# hm2_redraw.net
KiCad netlist of a schematic drawn in EAGLE
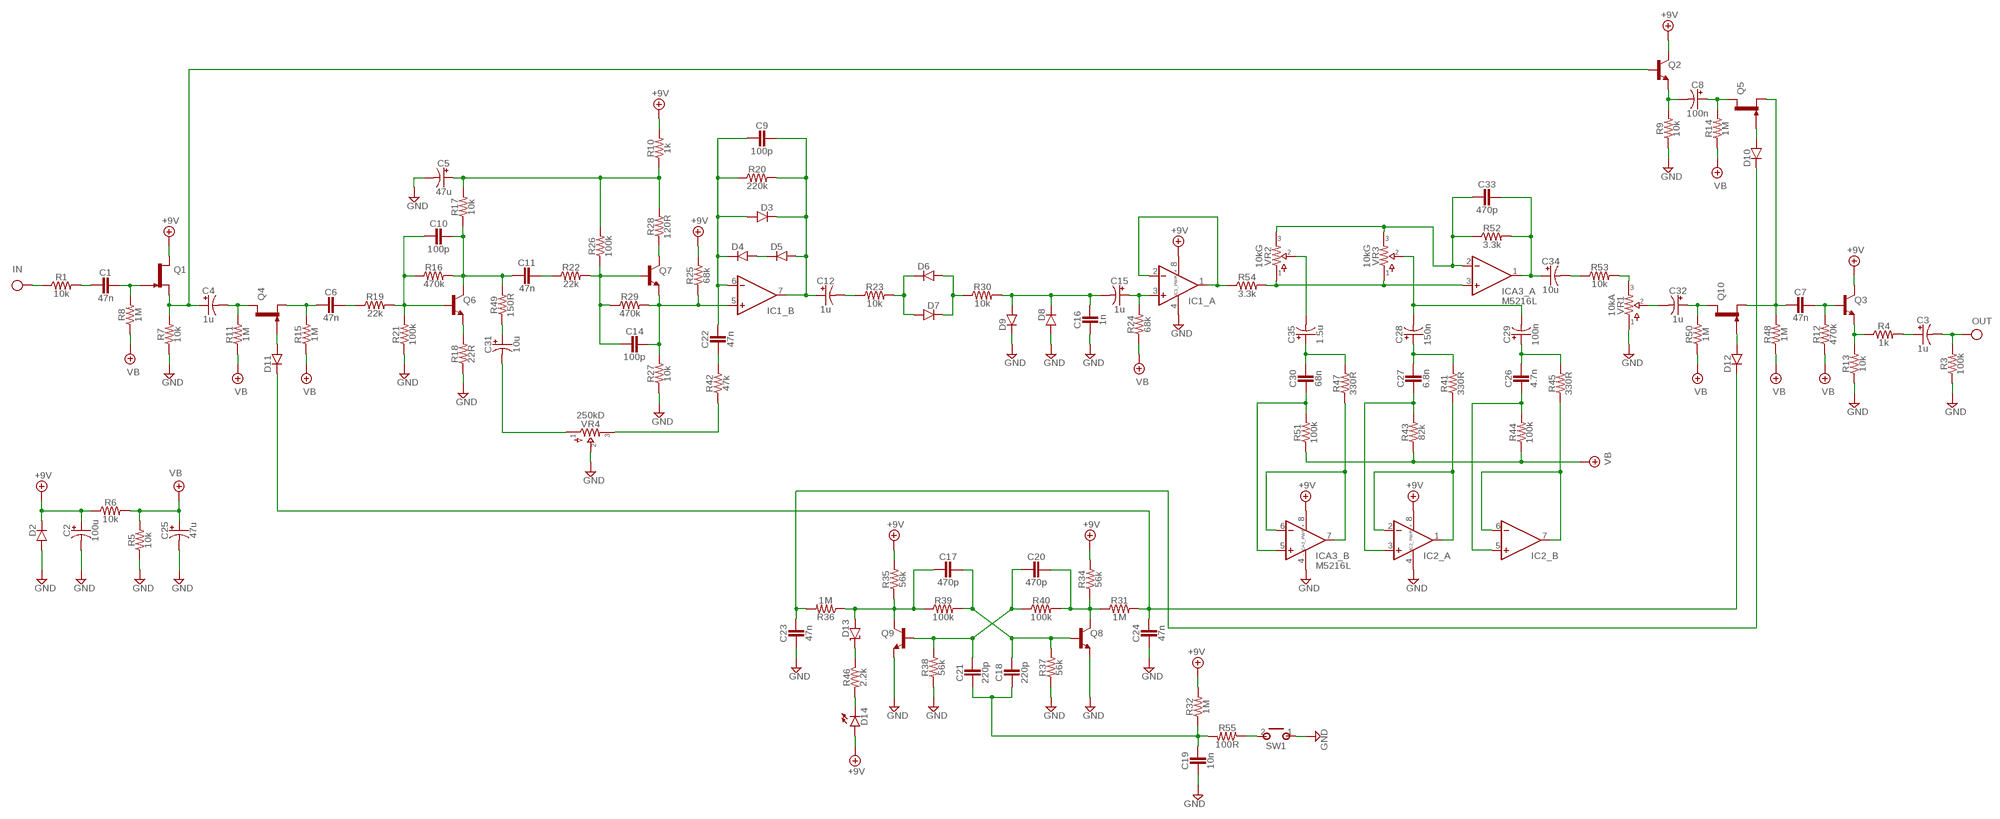
[diagram p0: schematic, sheet 1]

(export (version "E")
  (design (tool "Eeschema 10.0.6"))
  (components
    (comp (ref "C1")
      (value "47n")
      (footprint "eagle-import:BOX_SMALL")
      (libsource (lib "eagle-import") (part "CER/FILMBOX.1"))
    )
    (comp (ref "C2")
      (value "100u")
      (footprint "eagle-import:040_020")
      (libsource (lib "eagle-import") (part "0400"))
    )
    (comp (ref "C3")
      (value "1u")
      (footprint "eagle-import:040_020")
      (libsource (lib "eagle-import") (part "0400"))
    )
    (comp (ref "C4")
      (value "1u")
      (footprint "eagle-import:040_020")
      (libsource (lib "eagle-import") (part "0400"))
    )
    (comp (ref "C5")
      (value "47u")
      (footprint "eagle-import:040_020")
      (libsource (lib "eagle-import") (part "0400"))
    )
    (comp (ref "C6")
      (value "47n")
      (footprint "eagle-import:BOX_SMALL")
      (libsource (lib "eagle-import") (part "CER/FILMBOX.1"))
    )
    (comp (ref "C7")
      (value "47n")
      (footprint "eagle-import:BOX_SMALL")
      (libsource (lib "eagle-import") (part "CER/FILMBOX.1"))
    )
    (comp (ref "C8")
      (value "100n")
      (footprint "eagle-import:040_020")
      (libsource (lib "eagle-import") (part "0400"))
    )
    (comp (ref "C9")
      (value "100p")
      (footprint "eagle-import:BOX_SMALL")
      (libsource (lib "eagle-import") (part "CER/FILMBOX.1"))
    )
    (comp (ref "C10")
      (value "100p")
      (footprint "eagle-import:BOX_SMALL")
      (libsource (lib "eagle-import") (part "CER/FILMBOX.1"))
    )
    (comp (ref "C11")
      (value "47n")
      (footprint "eagle-import:BOX_SMALL")
      (libsource (lib "eagle-import") (part "CER/FILMBOX.1"))
    )
    (comp (ref "C12")
      (value "1u")
      (footprint "eagle-import:040_020")
      (libsource (lib "eagle-import") (part "0400"))
    )
    (comp (ref "C14")
      (value "100p")
      (footprint "eagle-import:BOX_SMALL")
      (libsource (lib "eagle-import") (part "CER/FILMBOX.1"))
    )
    (comp (ref "C15")
      (value "1u")
      (footprint "eagle-import:040_020")
      (libsource (lib "eagle-import") (part "0400"))
    )
    (comp (ref "C16")
      (value "1n")
      (footprint "eagle-import:BOX_SMALL")
      (libsource (lib "eagle-import") (part "CER/FILMBOX.1"))
    )
    (comp (ref "C17")
      (value "470p")
      (footprint "eagle-import:BOX_SMALL")
      (libsource (lib "eagle-import") (part "CER/FILMBOX.1"))
    )
    (comp (ref "C18")
      (value "220p")
      (footprint "eagle-import:BOX_SMALL")
      (libsource (lib "eagle-import") (part "CER/FILMBOX.1"))
    )
    (comp (ref "C19")
      (value "10n")
      (footprint "eagle-import:BOX_SMALL")
      (libsource (lib "eagle-import") (part "CER/FILMBOX.1"))
    )
    (comp (ref "C20")
      (value "470p")
      (footprint "eagle-import:BOX_SMALL")
      (libsource (lib "eagle-import") (part "CER/FILMBOX.1"))
    )
    (comp (ref "C21")
      (value "220p")
      (footprint "eagle-import:BOX_SMALL")
      (libsource (lib "eagle-import") (part "CER/FILMBOX.1"))
    )
    (comp (ref "C22")
      (value "47n")
      (footprint "eagle-import:BOX_SMALL")
      (libsource (lib "eagle-import") (part "CER/FILMBOX.1"))
    )
    (comp (ref "C23")
      (value "47n")
      (footprint "eagle-import:BOX_SMALL")
      (libsource (lib "eagle-import") (part "CER/FILMBOX.1"))
    )
    (comp (ref "C24")
      (value "47n")
      (footprint "eagle-import:BOX_SMALL")
      (libsource (lib "eagle-import") (part "CER/FILMBOX.1"))
    )
    (comp (ref "C25")
      (value "47u")
      (footprint "eagle-import:040_020")
      (libsource (lib "eagle-import") (part "0400"))
    )
    (comp (ref "C26")
      (value "4.7n")
      (footprint "eagle-import:BOX_SMALL")
      (libsource (lib "eagle-import") (part "CER/FILMBOX.1"))
    )
    (comp (ref "C27")
      (value "6.8n")
      (footprint "eagle-import:BOX_SMALL")
      (libsource (lib "eagle-import") (part "CER/FILMBOX.1"))
    )
    (comp (ref "C28")
      (value "150n")
      (footprint "eagle-import:040_020")
      (libsource (lib "eagle-import") (part "0400"))
    )
    (comp (ref "C29")
      (value "100n")
      (footprint "eagle-import:040_020")
      (libsource (lib "eagle-import") (part "0400"))
    )
    (comp (ref "C30")
      (value "68n")
      (footprint "eagle-import:BOX_SMALL")
      (libsource (lib "eagle-import") (part "CER/FILMBOX.1"))
    )
    (comp (ref "C31")
      (value "10u")
      (footprint "eagle-import:040_020")
      (libsource (lib "eagle-import") (part "0400"))
    )
    (comp (ref "C32")
      (value "1u")
      (footprint "eagle-import:040_020")
      (libsource (lib "eagle-import") (part "0400"))
    )
    (comp (ref "C33")
      (value "470p")
      (footprint "eagle-import:BOX_SMALL")
      (libsource (lib "eagle-import") (part "CER/FILMBOX.1"))
    )
    (comp (ref "C34")
      (value "10u")
      (footprint "eagle-import:040_020")
      (libsource (lib "eagle-import") (part "0400"))
    )
    (comp (ref "C35")
      (value "1.5u")
      (footprint "eagle-import:040_020")
      (libsource (lib "eagle-import") (part "0400"))
    )
    (comp (ref "D2")
      (value "DO35.2")
      (footprint "eagle-import:DO35-2")
      (libsource (lib "eagle-import") (part "DO35.2"))
    )
    (comp (ref "D3")
      (value "DO35.2")
      (footprint "eagle-import:DO35-2")
      (libsource (lib "eagle-import") (part "DO35.2"))
    )
    (comp (ref "D4")
      (value "DO35.2")
      (footprint "eagle-import:DO35-2")
      (libsource (lib "eagle-import") (part "DO35.2"))
    )
    (comp (ref "D5")
      (value "DO35.2")
      (footprint "eagle-import:DO35-2")
      (libsource (lib "eagle-import") (part "DO35.2"))
    )
    (comp (ref "D6")
      (value "DO35.2")
      (footprint "eagle-import:DO35-2")
      (libsource (lib "eagle-import") (part "DO35.2"))
    )
    (comp (ref "D7")
      (value "DO35.2")
      (footprint "eagle-import:DO35-2")
      (libsource (lib "eagle-import") (part "DO35.2"))
    )
    (comp (ref "D8")
      (value "DO35.2")
      (footprint "eagle-import:DO35-2")
      (libsource (lib "eagle-import") (part "DO35.2"))
    )
    (comp (ref "D9")
      (value "DO35.2")
      (footprint "eagle-import:DO35-2")
      (libsource (lib "eagle-import") (part "DO35.2"))
    )
    (comp (ref "D10")
      (value "DO35.2")
      (footprint "eagle-import:DO35-2")
      (libsource (lib "eagle-import") (part "DO35.2"))
    )
    (comp (ref "D11")
      (value "DO35.2")
      (footprint "eagle-import:DO35-2")
      (libsource (lib "eagle-import") (part "DO35.2"))
    )
    (comp (ref "D12")
      (value "DO35.2")
      (footprint "eagle-import:DO35-2")
      (libsource (lib "eagle-import") (part "DO35.2"))
    )
    (comp (ref "D13")
      (value "ZENER.2")
      (footprint "eagle-import:DO41-2")
      (libsource (lib "eagle-import") (part "ZENER.2"))
    )
    (comp (ref "D14")
      (value "LED")
      (footprint "eagle-import:3MM_D")
      (libsource (lib "eagle-import") (part "LED"))
    )
    (comp (ref "IC1")
      (value "DUALTH")
      (footprint "eagle-import:DIL0")
      (libsource (lib "eagle-import") (part "DUALTH"))
    )
    (comp (ref "IC2")
      (value "DUALTH")
      (footprint "eagle-import:DIL0")
      (libsource (lib "eagle-import") (part "DUALTH"))
    )
    (comp (ref "ICA3")
      (value "M5216L")
      (footprint "eagle-import:DIL0")
      (libsource (lib "eagle-import") (part "DUALTH"))
    )
    (comp (ref "Q1")
      (value "2N5457")
      (footprint "eagle-import:TO92-")
      (libsource (lib "eagle-import") (part "2N5457"))
    )
    (comp (ref "Q2")
      (value "2SC828A")
      (footprint "eagle-import:TO92-")
      (libsource (lib "eagle-import") (part "2SC828A"))
    )
    (comp (ref "Q3")
      (value "2SC828A")
      (footprint "eagle-import:TO92-")
      (libsource (lib "eagle-import") (part "2SC828A"))
    )
    (comp (ref "Q4")
      (value "2N5457")
      (footprint "eagle-import:TO92-")
      (libsource (lib "eagle-import") (part "2N5457"))
    )
    (comp (ref "Q5")
      (value "2N5457")
      (footprint "eagle-import:TO92-")
      (libsource (lib "eagle-import") (part "2N5457"))
    )
    (comp (ref "Q6")
      (value "2SC828A")
      (footprint "eagle-import:TO92-")
      (libsource (lib "eagle-import") (part "2SC828A"))
    )
    (comp (ref "Q7")
      (value "2SC828A")
      (footprint "eagle-import:TO92-")
      (libsource (lib "eagle-import") (part "2SC828A"))
    )
    (comp (ref "Q8")
      (value "2SC828A")
      (footprint "eagle-import:TO92-")
      (libsource (lib "eagle-import") (part "2SC828A"))
    )
    (comp (ref "Q9")
      (value "2SC828A")
      (footprint "eagle-import:TO92-")
      (libsource (lib "eagle-import") (part "2SC828A"))
    )
    (comp (ref "Q10")
      (value "2N5457")
      (footprint "eagle-import:TO92-")
      (libsource (lib "eagle-import") (part "2N5457"))
    )
    (comp (ref "R1")
      (value "10k")
      (footprint "eagle-import:R0207_3")
      (libsource (lib "eagle-import") (part "R_.3B"))
    )
    (comp (ref "R3")
      (value "100k")
      (footprint "eagle-import:R0207_3")
      (libsource (lib "eagle-import") (part "R_.3B"))
    )
    (comp (ref "R4")
      (value "1k")
      (footprint "eagle-import:R0207_3")
      (libsource (lib "eagle-import") (part "R_.3B"))
    )
    (comp (ref "R5")
      (value "10k")
      (footprint "eagle-import:R0207_3")
      (libsource (lib "eagle-import") (part "R_.3B"))
    )
    (comp (ref "R6")
      (value "10k")
      (footprint "eagle-import:R0207_3")
      (libsource (lib "eagle-import") (part "R_.3B"))
    )
    (comp (ref "R7")
      (value "10k")
      (footprint "eagle-import:R0207_3")
      (libsource (lib "eagle-import") (part "R_.3B"))
    )
    (comp (ref "R8")
      (value "1M")
      (footprint "eagle-import:R0207_3")
      (libsource (lib "eagle-import") (part "R_.3B"))
    )
    (comp (ref "R9")
      (value "10k")
      (footprint "eagle-import:R0207_3")
      (libsource (lib "eagle-import") (part "R_.3B"))
    )
    (comp (ref "R10")
      (value "1k")
      (footprint "eagle-import:R0207_3")
      (libsource (lib "eagle-import") (part "R_.3B"))
    )
    (comp (ref "R11")
      (value "1M")
      (footprint "eagle-import:R0207_3")
      (libsource (lib "eagle-import") (part "R_.3B"))
    )
    (comp (ref "R12")
      (value "470k")
      (footprint "eagle-import:R0207_3")
      (libsource (lib "eagle-import") (part "R_.3B"))
    )
    (comp (ref "R13")
      (value "10k")
      (footprint "eagle-import:R0207_3")
      (libsource (lib "eagle-import") (part "R_.3B"))
    )
    (comp (ref "R14")
      (value "1M")
      (footprint "eagle-import:R0207_3")
      (libsource (lib "eagle-import") (part "R_.3B"))
    )
    (comp (ref "R15")
      (value "1M")
      (footprint "eagle-import:R0207_3")
      (libsource (lib "eagle-import") (part "R_.3B"))
    )
    (comp (ref "R16")
      (value "470k")
      (footprint "eagle-import:R0207_3")
      (libsource (lib "eagle-import") (part "R_.3B"))
    )
    (comp (ref "R17")
      (value "10k")
      (footprint "eagle-import:R0207_3")
      (libsource (lib "eagle-import") (part "R_.3B"))
    )
    (comp (ref "R18")
      (value "22R")
      (footprint "eagle-import:R0207_3")
      (libsource (lib "eagle-import") (part "R_.3B"))
    )
    (comp (ref "R19")
      (value "22k")
      (footprint "eagle-import:R0207_3")
      (libsource (lib "eagle-import") (part "R_.3B"))
    )
    (comp (ref "R20")
      (value "220k")
      (footprint "eagle-import:R0207_3")
      (libsource (lib "eagle-import") (part "R_.3B"))
    )
    (comp (ref "R21")
      (value "100k")
      (footprint "eagle-import:R0207_3")
      (libsource (lib "eagle-import") (part "R_.3B"))
    )
    (comp (ref "R22")
      (value "22k")
      (footprint "eagle-import:R0207_3")
      (libsource (lib "eagle-import") (part "R_.3B"))
    )
    (comp (ref "R23")
      (value "10k")
      (footprint "eagle-import:R0207_3")
      (libsource (lib "eagle-import") (part "R_.3B"))
    )
    (comp (ref "R24")
      (value "68k")
      (footprint "eagle-import:R0207_3")
      (libsource (lib "eagle-import") (part "R_.3B"))
    )
    (comp (ref "R25")
      (value "68k")
      (footprint "eagle-import:R0207_3")
      (libsource (lib "eagle-import") (part "R_.3B"))
    )
    (comp (ref "R26")
      (value "100k")
      (footprint "eagle-import:R0207_3")
      (libsource (lib "eagle-import") (part "R_.3B"))
    )
    (comp (ref "R27")
      (value "10k")
      (footprint "eagle-import:R0207_3")
      (libsource (lib "eagle-import") (part "R_.3B"))
    )
    (comp (ref "R28")
      (value "120R")
      (footprint "eagle-import:R0207_3")
      (libsource (lib "eagle-import") (part "R_.3B"))
    )
    (comp (ref "R29")
      (value "470k")
      (footprint "eagle-import:R0207_3")
      (libsource (lib "eagle-import") (part "R_.3B"))
    )
    (comp (ref "R30")
      (value "10k")
      (footprint "eagle-import:R0207_3")
      (libsource (lib "eagle-import") (part "R_.3B"))
    )
    (comp (ref "R31")
      (value "1M")
      (footprint "eagle-import:R0207_3")
      (libsource (lib "eagle-import") (part "R_.3B"))
    )
    (comp (ref "R32")
      (value "1M")
      (footprint "eagle-import:R0207_3")
      (libsource (lib "eagle-import") (part "R_.3B"))
    )
    (comp (ref "R34")
      (value "56k")
      (footprint "eagle-import:R0207_3")
      (libsource (lib "eagle-import") (part "R_.3B"))
    )
    (comp (ref "R35")
      (value "56k")
      (footprint "eagle-import:R0207_3")
      (libsource (lib "eagle-import") (part "R_.3B"))
    )
    (comp (ref "R36")
      (value "1M")
      (footprint "eagle-import:R0207_3")
      (libsource (lib "eagle-import") (part "R_.3B"))
    )
    (comp (ref "R37")
      (value "56k")
      (footprint "eagle-import:R0207_3")
      (libsource (lib "eagle-import") (part "R_.3B"))
    )
    (comp (ref "R38")
      (value "56k")
      (footprint "eagle-import:R0207_3")
      (libsource (lib "eagle-import") (part "R_.3B"))
    )
    (comp (ref "R39")
      (value "100k")
      (footprint "eagle-import:R0207_3")
      (libsource (lib "eagle-import") (part "R_.3B"))
    )
    (comp (ref "R40")
      (value "100k")
      (footprint "eagle-import:R0207_3")
      (libsource (lib "eagle-import") (part "R_.3B"))
    )
    (comp (ref "R41")
      (value "330R")
      (footprint "eagle-import:R0207_3")
      (libsource (lib "eagle-import") (part "R_.3B"))
    )
    (comp (ref "R42")
      (value "47k")
      (footprint "eagle-import:R0207_3")
      (libsource (lib "eagle-import") (part "R_.3B"))
    )
    (comp (ref "R43")
      (value "82k")
      (footprint "eagle-import:R0207_3")
      (libsource (lib "eagle-import") (part "R_.3B"))
    )
    (comp (ref "R44")
      (value "100k")
      (footprint "eagle-import:R0207_3")
      (libsource (lib "eagle-import") (part "R_.3B"))
    )
    (comp (ref "R45")
      (value "330R")
      (footprint "eagle-import:R0207_3")
      (libsource (lib "eagle-import") (part "R_.3B"))
    )
    (comp (ref "R46")
      (value "2.2k")
      (footprint "eagle-import:R0207_3")
      (libsource (lib "eagle-import") (part "R_.3B"))
    )
    (comp (ref "R47")
      (value "330R")
      (footprint "eagle-import:R0207_3")
      (libsource (lib "eagle-import") (part "R_.3B"))
    )
    (comp (ref "R48")
      (value "1M")
      (footprint "eagle-import:R0207_3")
      (libsource (lib "eagle-import") (part "R_.3B"))
    )
    (comp (ref "R49")
      (value "150R")
      (footprint "eagle-import:R0207_3")
      (libsource (lib "eagle-import") (part "R_.3B"))
    )
    (comp (ref "R50")
      (value "1M")
      (footprint "eagle-import:R0207_3")
      (libsource (lib "eagle-import") (part "R_.3B"))
    )
    (comp (ref "R51")
      (value "100k")
      (footprint "eagle-import:R0207_3")
      (libsource (lib "eagle-import") (part "R_.3B"))
    )
    (comp (ref "R52")
      (value "3.3k")
      (footprint "eagle-import:R0207_3")
      (libsource (lib "eagle-import") (part "R_.3B"))
    )
    (comp (ref "R53")
      (value "10k")
      (footprint "eagle-import:R0207_3")
      (libsource (lib "eagle-import") (part "R_.3B"))
    )
    (comp (ref "R54")
      (value "3.3k")
      (footprint "eagle-import:R0207_3")
      (libsource (lib "eagle-import") (part "R_.3B"))
    )
    (comp (ref "R55")
      (value "100R")
      (footprint "eagle-import:R0207_3")
      (libsource (lib "eagle-import") (part "R_.3B"))
    )
    (comp (ref "SW1")
      (value "MOMENTARY")
      (footprint "eagle-import:SPST")
      (libsource (lib "eagle-import") (part "MOMENTARY"))
    )
    (comp (ref "VR1")
      (value "10kA")
      (footprint "eagle-import:16MM")
      (libsource (lib "eagle-import") (part "POTS16MM"))
    )
    (comp (ref "VR2")
      (value "10kG")
      (footprint "eagle-import:16MM")
      (libsource (lib "eagle-import") (part "POTS16MM"))
    )
    (comp (ref "VR3")
      (value "10kG")
      (footprint "eagle-import:16MM")
      (libsource (lib "eagle-import") (part "POTS16MM"))
    )
    (comp (ref "VR4")
      (value "250kD")
      (footprint "eagle-import:16MM")
      (libsource (lib "eagle-import") (part "POTS16MM"))
    )
  )
  (nets
    (net (code "1") (name "+9V") (class "Default")
      (node (ref "C2") (pin "+") (pinfunction "+_+") (pintype "passive"))
      (node (ref "D14") (pin "ANODE") (pinfunction "A_ANODE") (pintype "passive"))
      (node (ref "D2") (pin "C") (pinfunction "C_C") (pintype "passive"))
      (node (ref "IC1") (pin "8") (pinfunction "V+_8") (pintype "power_in"))
      (node (ref "IC2") (pin "8") (pinfunction "V+_8") (pintype "power_in"))
      (node (ref "ICA3") (pin "8") (pinfunction "V+_8") (pintype "power_in"))
      (node (ref "Q1") (pin "3") (pinfunction "D_3") (pintype "passive"))
      (node (ref "Q2") (pin "2") (pinfunction "C_2") (pintype "passive"))
      (node (ref "Q3") (pin "2") (pinfunction "C_2") (pintype "passive"))
      (node (ref "R10") (pin "2") (pinfunction "2_2") (pintype "passive"))
      (node (ref "R25") (pin "2") (pinfunction "2_2") (pintype "passive"))
      (node (ref "R32") (pin "2") (pinfunction "2_2") (pintype "passive"))
      (node (ref "R34") (pin "2") (pinfunction "2_2") (pintype "passive"))
      (node (ref "R35") (pin "2") (pinfunction "2_2") (pintype "passive"))
      (node (ref "R6") (pin "1") (pinfunction "1_1") (pintype "passive"))
    )
    (net (code "2") (name "GND") (class "Default")
      (node (ref "C16") (pin "2") (pinfunction "2_2") (pintype "passive"))
      (node (ref "C19") (pin "2") (pinfunction "2_2") (pintype "passive"))
      (node (ref "C2") (pin "-") (pinfunction "-_-") (pintype "passive"))
      (node (ref "C23") (pin "2") (pinfunction "2_2") (pintype "passive"))
      (node (ref "C24") (pin "2") (pinfunction "2_2") (pintype "passive"))
      (node (ref "C25") (pin "-") (pinfunction "-_-") (pintype "passive"))
      (node (ref "C5") (pin "-") (pinfunction "-_-") (pintype "passive"))
      (node (ref "D2") (pin "A") (pinfunction "A_A") (pintype "passive"))
      (node (ref "D8") (pin "A") (pinfunction "A_A") (pintype "passive"))
      (node (ref "D9") (pin "C") (pinfunction "C_C") (pintype "passive"))
      (node (ref "IC1") (pin "4") (pinfunction "V-_4") (pintype "power_in"))
      (node (ref "IC2") (pin "4") (pinfunction "V-_4") (pintype "power_in"))
      (node (ref "ICA3") (pin "4") (pinfunction "V-_4") (pintype "power_in"))
      (node (ref "Q8") (pin "3") (pinfunction "E_3") (pintype "passive"))
      (node (ref "Q9") (pin "3") (pinfunction "E_3") (pintype "passive"))
      (node (ref "R13") (pin "1") (pinfunction "1_1") (pintype "passive"))
      (node (ref "R18") (pin "1") (pinfunction "1_1") (pintype "passive"))
      (node (ref "R21") (pin "1") (pinfunction "1_1") (pintype "passive"))
      (node (ref "R27") (pin "1") (pinfunction "1_1") (pintype "passive"))
      (node (ref "R3") (pin "1") (pinfunction "1_1") (pintype "passive"))
      (node (ref "R37") (pin "1") (pinfunction "1_1") (pintype "passive"))
      (node (ref "R38") (pin "1") (pinfunction "1_1") (pintype "passive"))
      (node (ref "R5") (pin "1") (pinfunction "1_1") (pintype "passive"))
      (node (ref "R7") (pin "1") (pinfunction "1_1") (pintype "passive"))
      (node (ref "R9") (pin "1") (pinfunction "1_1") (pintype "passive"))
      (node (ref "SW1") (pin "1") (pinfunction "P_1") (pintype "passive"))
      (node (ref "VR1") (pin "1") (pinfunction "1_1") (pintype "passive"))
      (node (ref "VR4") (pin "2") (pinfunction "2_2") (pintype "passive"))
    )
    (net (code "3") (name "IN") (class "Default")
      (node (ref "R1") (pin "1") (pinfunction "1_1") (pintype "passive"))
    )
    (net (code "4") (name "Net-(C1-Pad2)") (class "Default")
      (node (ref "C1") (pin "2") (pinfunction "2_2") (pintype "passive"))
      (node (ref "R1") (pin "2") (pinfunction "2_2") (pintype "passive"))
    )
    (net (code "5") (name "Net-(C3-Pad+)") (class "Default")
      (node (ref "C3") (pin "+") (pinfunction "+_+") (pintype "passive"))
      (node (ref "R4") (pin "2") (pinfunction "2_2") (pintype "passive"))
    )
    (net (code "6") (name "Net-(C5-Pad+)") (class "Default")
      (node (ref "C5") (pin "+") (pinfunction "+_+") (pintype "passive"))
      (node (ref "R10") (pin "1") (pinfunction "1_1") (pintype "passive"))
      (node (ref "R17") (pin "2") (pinfunction "2_2") (pintype "passive"))
      (node (ref "R26") (pin "2") (pinfunction "2_2") (pintype "passive"))
      (node (ref "R28") (pin "2") (pinfunction "2_2") (pintype "passive"))
    )
    (net (code "7") (name "Net-(C6-Pad1)") (class "Default")
      (node (ref "C6") (pin "1") (pinfunction "1_1") (pintype "passive"))
      (node (ref "R19") (pin "1") (pinfunction "1_1") (pintype "passive"))
    )
    (net (code "8") (name "Net-(C11-Pad1)") (class "Default")
      (node (ref "C11") (pin "1") (pinfunction "1_1") (pintype "passive"))
      (node (ref "R22") (pin "1") (pinfunction "1_1") (pintype "passive"))
    )
    (net (code "9") (name "Net-(C12-Pad-)") (class "Default")
      (node (ref "C12") (pin "-") (pinfunction "-_-") (pintype "passive"))
      (node (ref "R23") (pin "1") (pinfunction "1_1") (pintype "passive"))
    )
    (net (code "10") (name "Net-(C15-Pad-)") (class "Default")
      (node (ref "C15") (pin "-") (pinfunction "-_-") (pintype "passive"))
      (node (ref "C16") (pin "1") (pinfunction "1_1") (pintype "passive"))
      (node (ref "D8") (pin "C") (pinfunction "C_C") (pintype "passive"))
      (node (ref "D9") (pin "A") (pinfunction "A_A") (pintype "passive"))
      (node (ref "R30") (pin "2") (pinfunction "2_2") (pintype "passive"))
    )
    (net (code "11") (name "Net-(C18-Pad2)") (class "Default")
      (node (ref "C18") (pin "2") (pinfunction "2_2") (pintype "passive"))
      (node (ref "C19") (pin "1") (pinfunction "1_1") (pintype "passive"))
      (node (ref "C21") (pin "2") (pinfunction "2_2") (pintype "passive"))
      (node (ref "R32") (pin "1") (pinfunction "1_1") (pintype "passive"))
      (node (ref "R55") (pin "2") (pinfunction "2_2") (pintype "passive"))
    )
    (net (code "12") (name "Net-(C22-Pad2)") (class "Default")
      (node (ref "C22") (pin "2") (pinfunction "2_2") (pintype "passive"))
      (node (ref "R42") (pin "2") (pinfunction "2_2") (pintype "passive"))
    )
    (net (code "13") (name "Net-(C23-Pad1)") (class "Default")
      (node (ref "C23") (pin "1") (pinfunction "1_1") (pintype "passive"))
      (node (ref "D10") (pin "C") (pinfunction "C_C") (pintype "passive"))
      (node (ref "R36") (pin "2") (pinfunction "2_2") (pintype "passive"))
    )
    (net (code "14") (name "Net-(C24-Pad1)") (class "Default")
      (node (ref "C24") (pin "1") (pinfunction "1_1") (pintype "passive"))
      (node (ref "D11") (pin "C") (pinfunction "C_C") (pintype "passive"))
      (node (ref "D12") (pin "C") (pinfunction "C_C") (pintype "passive"))
      (node (ref "R31") (pin "2") (pinfunction "2_2") (pintype "passive"))
    )
    (net (code "15") (name "Net-(C26-Pad1)") (class "Default")
      (node (ref "C26") (pin "1") (pinfunction "1_1") (pintype "passive"))
      (node (ref "C29") (pin "+") (pinfunction "+_+") (pintype "passive"))
      (node (ref "R45") (pin "2") (pinfunction "2_2") (pintype "passive"))
    )
    (net (code "16") (name "Net-(C27-Pad1)") (class "Default")
      (node (ref "C27") (pin "1") (pinfunction "1_1") (pintype "passive"))
      (node (ref "C28") (pin "+") (pinfunction "+_+") (pintype "passive"))
      (node (ref "R41") (pin "2") (pinfunction "2_2") (pintype "passive"))
    )
    (net (code "17") (name "Net-(C28-Pad-)") (class "Default")
      (node (ref "C28") (pin "-") (pinfunction "-_-") (pintype "passive"))
      (node (ref "C29") (pin "-") (pinfunction "-_-") (pintype "passive"))
      (node (ref "VR3") (pin "2") (pinfunction "2_2") (pintype "passive"))
    )
    (net (code "18") (name "Net-(C30-Pad1)") (class "Default")
      (node (ref "C30") (pin "1") (pinfunction "1_1") (pintype "passive"))
      (node (ref "C35") (pin "+") (pinfunction "+_+") (pintype "passive"))
      (node (ref "R47") (pin "2") (pinfunction "2_2") (pintype "passive"))
    )
    (net (code "19") (name "Net-(C31-Pad+)") (class "Default")
      (node (ref "C31") (pin "+") (pinfunction "+_+") (pintype "passive"))
      (node (ref "R49") (pin "1") (pinfunction "1_1") (pintype "passive"))
    )
    (net (code "20") (name "Net-(C31-Pad-)") (class "Default")
      (node (ref "C31") (pin "-") (pinfunction "-_-") (pintype "passive"))
      (node (ref "VR4") (pin "1") (pinfunction "1_1") (pintype "passive"))
    )
    (net (code "21") (name "Net-(C32-Pad-)") (class "Default")
      (node (ref "C32") (pin "-") (pinfunction "-_-") (pintype "passive"))
      (node (ref "VR1") (pin "2") (pinfunction "2_2") (pintype "passive"))
    )
    (net (code "22") (name "Net-(C34-Pad-)") (class "Default")
      (node (ref "C34") (pin "-") (pinfunction "-_-") (pintype "passive"))
      (node (ref "R53") (pin "1") (pinfunction "1_1") (pintype "passive"))
    )
    (net (code "23") (name "Net-(C35-Pad-)") (class "Default")
      (node (ref "C35") (pin "-") (pinfunction "-_-") (pintype "passive"))
      (node (ref "VR2") (pin "2") (pinfunction "2_2") (pintype "passive"))
    )
    (net (code "24") (name "Net-(D4-PadA)") (class "Default")
      (node (ref "D4") (pin "A") (pinfunction "A_A") (pintype "passive"))
      (node (ref "D5") (pin "C") (pinfunction "C_C") (pintype "passive"))
    )
    (net (code "25") (name "Net-(D6-PadA)") (class "Default")
      (node (ref "D6") (pin "A") (pinfunction "A_A") (pintype "passive"))
      (node (ref "D7") (pin "C") (pinfunction "C_C") (pintype "passive"))
      (node (ref "R30") (pin "1") (pinfunction "1_1") (pintype "passive"))
    )
    (net (code "26") (name "Net-(D6-PadC)") (class "Default")
      (node (ref "D6") (pin "C") (pinfunction "C_C") (pintype "passive"))
      (node (ref "D7") (pin "A") (pinfunction "A_A") (pintype "passive"))
      (node (ref "R23") (pin "2") (pinfunction "2_2") (pintype "passive"))
    )
    (net (code "27") (name "Net-(D13-PadC)") (class "Default")
      (node (ref "D13") (pin "C") (pinfunction "C_C") (pintype "passive"))
      (node (ref "R46") (pin "1") (pinfunction "1_1") (pintype "passive"))
    )
    (net (code "28") (name "Net-(D14-C)") (class "Default")
      (node (ref "D14") (pin "P$1") (pinfunction "C_P$1") (pintype "passive"))
      (node (ref "R46") (pin "2") (pinfunction "2_2") (pintype "passive"))
    )
    (net (code "29") (name "Net-(IC1A-+IN)") (class "Default")
      (node (ref "C15") (pin "+") (pinfunction "+_+") (pintype "passive"))
      (node (ref "IC1") (pin "3") (pinfunction "+IN_3") (pintype "input"))
      (node (ref "R24") (pin "2") (pinfunction "2_2") (pintype "passive"))
    )
    (net (code "30") (name "Net-(IC1A--IN)") (class "Default")
      (node (ref "IC1") (pin "1") (pinfunction "OUT_1") (pintype "output"))
      (node (ref "IC1") (pin "2") (pinfunction "-IN_2") (pintype "input"))
      (node (ref "R54") (pin "1") (pinfunction "1_1") (pintype "passive"))
    )
    (net (code "31") (name "Net-(IC1B-+IN)") (class "Default")
      (node (ref "C14") (pin "1") (pinfunction "1_1") (pintype "passive"))
      (node (ref "IC1") (pin "5") (pinfunction "+IN_5") (pintype "input"))
      (node (ref "Q7") (pin "3") (pinfunction "E_3") (pintype "passive"))
      (node (ref "R25") (pin "1") (pinfunction "1_1") (pintype "passive"))
      (node (ref "R27") (pin "2") (pinfunction "2_2") (pintype "passive"))
      (node (ref "R29") (pin "2") (pinfunction "2_2") (pintype "passive"))
    )
    (net (code "32") (name "Net-(IC1B--IN)") (class "Default")
      (node (ref "C22") (pin "1") (pinfunction "1_1") (pintype "passive"))
      (node (ref "C9") (pin "2") (pinfunction "2_2") (pintype "passive"))
      (node (ref "D3") (pin "A") (pinfunction "A_A") (pintype "passive"))
      (node (ref "D4") (pin "C") (pinfunction "C_C") (pintype "passive"))
      (node (ref "IC1") (pin "6") (pinfunction "-IN_6") (pintype "input"))
      (node (ref "R20") (pin "1") (pinfunction "1_1") (pintype "passive"))
    )
    (net (code "33") (name "Net-(IC1B-OUT)") (class "Default")
      (node (ref "C12") (pin "+") (pinfunction "+_+") (pintype "passive"))
      (node (ref "C9") (pin "1") (pinfunction "1_1") (pintype "passive"))
      (node (ref "D3") (pin "C") (pinfunction "C_C") (pintype "passive"))
      (node (ref "D5") (pin "A") (pinfunction "A_A") (pintype "passive"))
      (node (ref "IC1") (pin "7") (pinfunction "OUT_7") (pintype "output"))
      (node (ref "R20") (pin "2") (pinfunction "2_2") (pintype "passive"))
    )
    (net (code "34") (name "Net-(IC2A-+IN)") (class "Default")
      (node (ref "C27") (pin "2") (pinfunction "2_2") (pintype "passive"))
      (node (ref "IC2") (pin "3") (pinfunction "+IN_3") (pintype "input"))
      (node (ref "R43") (pin "2") (pinfunction "2_2") (pintype "passive"))
    )
    (net (code "35") (name "Net-(IC2A--IN)") (class "Default")
      (node (ref "IC2") (pin "1") (pinfunction "OUT_1") (pintype "output"))
      (node (ref "IC2") (pin "2") (pinfunction "-IN_2") (pintype "input"))
      (node (ref "R41") (pin "1") (pinfunction "1_1") (pintype "passive"))
    )
    (net (code "36") (name "Net-(IC2B-+IN)") (class "Default")
      (node (ref "C26") (pin "2") (pinfunction "2_2") (pintype "passive"))
      (node (ref "IC2") (pin "5") (pinfunction "+IN_5") (pintype "input"))
      (node (ref "R44") (pin "2") (pinfunction "2_2") (pintype "passive"))
    )
    (net (code "37") (name "Net-(IC2B--IN)") (class "Default")
      (node (ref "IC2") (pin "6") (pinfunction "-IN_6") (pintype "input"))
      (node (ref "IC2") (pin "7") (pinfunction "OUT_7") (pintype "output"))
      (node (ref "R45") (pin "1") (pinfunction "1_1") (pintype "passive"))
    )
    (net (code "38") (name "Net-(ICA3A-+IN)") (class "Default")
      (node (ref "ICA3") (pin "3") (pinfunction "+IN_3") (pintype "input"))
      (node (ref "R54") (pin "2") (pinfunction "2_2") (pintype "passive"))
      (node (ref "VR2") (pin "1") (pinfunction "1_1") (pintype "passive"))
      (node (ref "VR3") (pin "1") (pinfunction "1_1") (pintype "passive"))
    )
    (net (code "39") (name "Net-(ICA3A--IN)") (class "Default")
      (node (ref "C33") (pin "2") (pinfunction "2_2") (pintype "passive"))
      (node (ref "ICA3") (pin "2") (pinfunction "-IN_2") (pintype "input"))
      (node (ref "R52") (pin "1") (pinfunction "1_1") (pintype "passive"))
      (node (ref "VR2") (pin "3") (pinfunction "3_3") (pintype "passive"))
      (node (ref "VR3") (pin "3") (pinfunction "3_3") (pintype "passive"))
    )
    (net (code "40") (name "Net-(ICA3A-OUT)") (class "Default")
      (node (ref "C33") (pin "1") (pinfunction "1_1") (pintype "passive"))
      (node (ref "C34") (pin "+") (pinfunction "+_+") (pintype "passive"))
      (node (ref "ICA3") (pin "1") (pinfunction "OUT_1") (pintype "output"))
      (node (ref "R52") (pin "2") (pinfunction "2_2") (pintype "passive"))
    )
    (net (code "41") (name "Net-(ICA3B-+IN)") (class "Default")
      (node (ref "C30") (pin "2") (pinfunction "2_2") (pintype "passive"))
      (node (ref "ICA3") (pin "5") (pinfunction "+IN_5") (pintype "input"))
      (node (ref "R51") (pin "2") (pinfunction "2_2") (pintype "passive"))
    )
    (net (code "42") (name "Net-(ICA3B--IN)") (class "Default")
      (node (ref "ICA3") (pin "6") (pinfunction "-IN_6") (pintype "input"))
      (node (ref "ICA3") (pin "7") (pinfunction "OUT_7") (pintype "output"))
      (node (ref "R47") (pin "1") (pinfunction "1_1") (pintype "passive"))
    )
    (net (code "43") (name "Net-(Q1-G)") (class "Default")
      (node (ref "C1") (pin "1") (pinfunction "1_1") (pintype "passive"))
      (node (ref "Q1") (pin "1") (pinfunction "G_1") (pintype "passive"))
      (node (ref "R8") (pin "2") (pinfunction "2_2") (pintype "passive"))
    )
    (net (code "44") (name "Net-(Q1-S)") (class "Default")
      (node (ref "C4") (pin "+") (pinfunction "+_+") (pintype "passive"))
      (node (ref "Q1") (pin "2") (pinfunction "S_2") (pintype "passive"))
      (node (ref "Q2") (pin "1") (pinfunction "B_1") (pintype "passive"))
      (node (ref "R7") (pin "2") (pinfunction "2_2") (pintype "passive"))
    )
    (net (code "45") (name "Net-(Q2-E)") (class "Default")
      (node (ref "C8") (pin "-") (pinfunction "-_-") (pintype "passive"))
      (node (ref "Q2") (pin "3") (pinfunction "E_3") (pintype "passive"))
      (node (ref "R9") (pin "2") (pinfunction "2_2") (pintype "passive"))
    )
    (net (code "46") (name "Net-(Q3-B)") (class "Default")
      (node (ref "C7") (pin "1") (pinfunction "1_1") (pintype "passive"))
      (node (ref "Q3") (pin "1") (pinfunction "B_1") (pintype "passive"))
      (node (ref "R12") (pin "2") (pinfunction "2_2") (pintype "passive"))
    )
    (net (code "47") (name "Net-(Q3-E)") (class "Default")
      (node (ref "Q3") (pin "3") (pinfunction "E_3") (pintype "passive"))
      (node (ref "R13") (pin "2") (pinfunction "2_2") (pintype "passive"))
      (node (ref "R4") (pin "1") (pinfunction "1_1") (pintype "passive"))
    )
    (net (code "48") (name "Net-(Q4-D)") (class "Default")
      (node (ref "C4") (pin "-") (pinfunction "-_-") (pintype "passive"))
      (node (ref "Q4") (pin "3") (pinfunction "D_3") (pintype "passive"))
      (node (ref "R11") (pin "2") (pinfunction "2_2") (pintype "passive"))
    )
    (net (code "49") (name "Net-(Q4-G)") (class "Default")
      (node (ref "D11") (pin "A") (pinfunction "A_A") (pintype "passive"))
      (node (ref "Q4") (pin "1") (pinfunction "G_1") (pintype "passive"))
    )
    (net (code "50") (name "Net-(Q4-S)") (class "Default")
      (node (ref "C6") (pin "2") (pinfunction "2_2") (pintype "passive"))
      (node (ref "Q4") (pin "2") (pinfunction "S_2") (pintype "passive"))
      (node (ref "R15") (pin "2") (pinfunction "2_2") (pintype "passive"))
    )
    (net (code "51") (name "Net-(Q5-D)") (class "Default")
      (node (ref "C8") (pin "+") (pinfunction "+_+") (pintype "passive"))
      (node (ref "Q5") (pin "3") (pinfunction "D_3") (pintype "passive"))
      (node (ref "R14") (pin "2") (pinfunction "2_2") (pintype "passive"))
    )
    (net (code "52") (name "Net-(Q5-G)") (class "Default")
      (node (ref "D10") (pin "A") (pinfunction "A_A") (pintype "passive"))
      (node (ref "Q5") (pin "1") (pinfunction "G_1") (pintype "passive"))
    )
    (net (code "53") (name "Net-(Q6-B)") (class "Default")
      (node (ref "C10") (pin "2") (pinfunction "2_2") (pintype "passive"))
      (node (ref "Q6") (pin "1") (pinfunction "B_1") (pintype "passive"))
      (node (ref "R16") (pin "1") (pinfunction "1_1") (pintype "passive"))
      (node (ref "R19") (pin "2") (pinfunction "2_2") (pintype "passive"))
      (node (ref "R21") (pin "2") (pinfunction "2_2") (pintype "passive"))
    )
    (net (code "54") (name "Net-(Q6-C)") (class "Default")
      (node (ref "C10") (pin "1") (pinfunction "1_1") (pintype "passive"))
      (node (ref "C11") (pin "2") (pinfunction "2_2") (pintype "passive"))
      (node (ref "Q6") (pin "2") (pinfunction "C_2") (pintype "passive"))
      (node (ref "R16") (pin "2") (pinfunction "2_2") (pintype "passive"))
      (node (ref "R17") (pin "1") (pinfunction "1_1") (pintype "passive"))
      (node (ref "R49") (pin "2") (pinfunction "2_2") (pintype "passive"))
    )
    (net (code "55") (name "Net-(Q6-E)") (class "Default")
      (node (ref "Q6") (pin "3") (pinfunction "E_3") (pintype "passive"))
      (node (ref "R18") (pin "2") (pinfunction "2_2") (pintype "passive"))
    )
    (net (code "56") (name "Net-(Q7-B)") (class "Default")
      (node (ref "C14") (pin "2") (pinfunction "2_2") (pintype "passive"))
      (node (ref "Q7") (pin "1") (pinfunction "B_1") (pintype "passive"))
      (node (ref "R22") (pin "2") (pinfunction "2_2") (pintype "passive"))
      (node (ref "R26") (pin "1") (pinfunction "1_1") (pintype "passive"))
      (node (ref "R29") (pin "1") (pinfunction "1_1") (pintype "passive"))
    )
    (net (code "57") (name "Net-(Q7-C)") (class "Default")
      (node (ref "Q7") (pin "2") (pinfunction "C_2") (pintype "passive"))
      (node (ref "R28") (pin "1") (pinfunction "1_1") (pintype "passive"))
    )
    (net (code "58") (name "Net-(Q8-B)") (class "Default")
      (node (ref "C17") (pin "1") (pinfunction "1_1") (pintype "passive"))
      (node (ref "C18") (pin "1") (pinfunction "1_1") (pintype "passive"))
      (node (ref "Q8") (pin "1") (pinfunction "B_1") (pintype "passive"))
      (node (ref "R37") (pin "2") (pinfunction "2_2") (pintype "passive"))
      (node (ref "R39") (pin "2") (pinfunction "2_2") (pintype "passive"))
    )
    (net (code "59") (name "Net-(Q8-C)") (class "Default")
      (node (ref "C20") (pin "1") (pinfunction "1_1") (pintype "passive"))
      (node (ref "Q8") (pin "2") (pinfunction "C_2") (pintype "passive"))
      (node (ref "R31") (pin "1") (pinfunction "1_1") (pintype "passive"))
      (node (ref "R34") (pin "1") (pinfunction "1_1") (pintype "passive"))
      (node (ref "R40") (pin "2") (pinfunction "2_2") (pintype "passive"))
    )
    (net (code "60") (name "Net-(Q9-B)") (class "Default")
      (node (ref "C20") (pin "2") (pinfunction "2_2") (pintype "passive"))
      (node (ref "C21") (pin "1") (pinfunction "1_1") (pintype "passive"))
      (node (ref "Q9") (pin "1") (pinfunction "B_1") (pintype "passive"))
      (node (ref "R38") (pin "2") (pinfunction "2_2") (pintype "passive"))
      (node (ref "R40") (pin "1") (pinfunction "1_1") (pintype "passive"))
    )
    (net (code "61") (name "Net-(Q9-C)") (class "Default")
      (node (ref "C17") (pin "2") (pinfunction "2_2") (pintype "passive"))
      (node (ref "D13") (pin "A") (pinfunction "A_A") (pintype "passive"))
      (node (ref "Q9") (pin "2") (pinfunction "C_2") (pintype "passive"))
      (node (ref "R35") (pin "1") (pinfunction "1_1") (pintype "passive"))
      (node (ref "R36") (pin "1") (pinfunction "1_1") (pintype "passive"))
      (node (ref "R39") (pin "1") (pinfunction "1_1") (pintype "passive"))
    )
    (net (code "62") (name "Net-(Q10-D)") (class "Default")
      (node (ref "C32") (pin "+") (pinfunction "+_+") (pintype "passive"))
      (node (ref "Q10") (pin "3") (pinfunction "D_3") (pintype "passive"))
      (node (ref "R50") (pin "2") (pinfunction "2_2") (pintype "passive"))
    )
    (net (code "63") (name "Net-(Q10-G)") (class "Default")
      (node (ref "D12") (pin "A") (pinfunction "A_A") (pintype "passive"))
      (node (ref "Q10") (pin "1") (pinfunction "G_1") (pintype "passive"))
    )
    (net (code "64") (name "Net-(Q10-S)") (class "Default")
      (node (ref "C7") (pin "2") (pinfunction "2_2") (pintype "passive"))
      (node (ref "Q10") (pin "2") (pinfunction "S_2") (pintype "passive"))
      (node (ref "Q5") (pin "2") (pinfunction "S_2") (pintype "passive"))
      (node (ref "R48") (pin "2") (pinfunction "2_2") (pintype "passive"))
    )
    (net (code "65") (name "Net-(R42-Pad1)") (class "Default")
      (node (ref "R42") (pin "1") (pinfunction "1_1") (pintype "passive"))
      (node (ref "VR4") (pin "3") (pinfunction "3_3") (pintype "passive"))
    )
    (net (code "66") (name "Net-(R53-Pad2)") (class "Default")
      (node (ref "R53") (pin "2") (pinfunction "2_2") (pintype "passive"))
      (node (ref "VR1") (pin "3") (pinfunction "3_3") (pintype "passive"))
    )
    (net (code "67") (name "Net-(SW1-S)") (class "Default")
      (node (ref "R55") (pin "1") (pinfunction "1_1") (pintype "passive"))
      (node (ref "SW1") (pin "2") (pinfunction "S_2") (pintype "passive"))
    )
    (net (code "68") (name "OUT") (class "Default")
      (node (ref "C3") (pin "-") (pinfunction "-_-") (pintype "passive"))
      (node (ref "R3") (pin "2") (pinfunction "2_2") (pintype "passive"))
    )
    (net (code "69") (name "VB") (class "Default")
      (node (ref "C25") (pin "+") (pinfunction "+_+") (pintype "passive"))
      (node (ref "R11") (pin "1") (pinfunction "1_1") (pintype "passive"))
      (node (ref "R12") (pin "1") (pinfunction "1_1") (pintype "passive"))
      (node (ref "R14") (pin "1") (pinfunction "1_1") (pintype "passive"))
      (node (ref "R15") (pin "1") (pinfunction "1_1") (pintype "passive"))
      (node (ref "R24") (pin "1") (pinfunction "1_1") (pintype "passive"))
      (node (ref "R43") (pin "1") (pinfunction "1_1") (pintype "passive"))
      (node (ref "R44") (pin "1") (pinfunction "1_1") (pintype "passive"))
      (node (ref "R48") (pin "1") (pinfunction "1_1") (pintype "passive"))
      (node (ref "R5") (pin "2") (pinfunction "2_2") (pintype "passive"))
      (node (ref "R50") (pin "1") (pinfunction "1_1") (pintype "passive"))
      (node (ref "R51") (pin "1") (pinfunction "1_1") (pintype "passive"))
      (node (ref "R6") (pin "2") (pinfunction "2_2") (pintype "passive"))
      (node (ref "R8") (pin "1") (pinfunction "1_1") (pintype "passive"))
    )
  )
)
